# 02_PWR_IN.net
KiCad netlist of a schematic drawn in Altium Designer
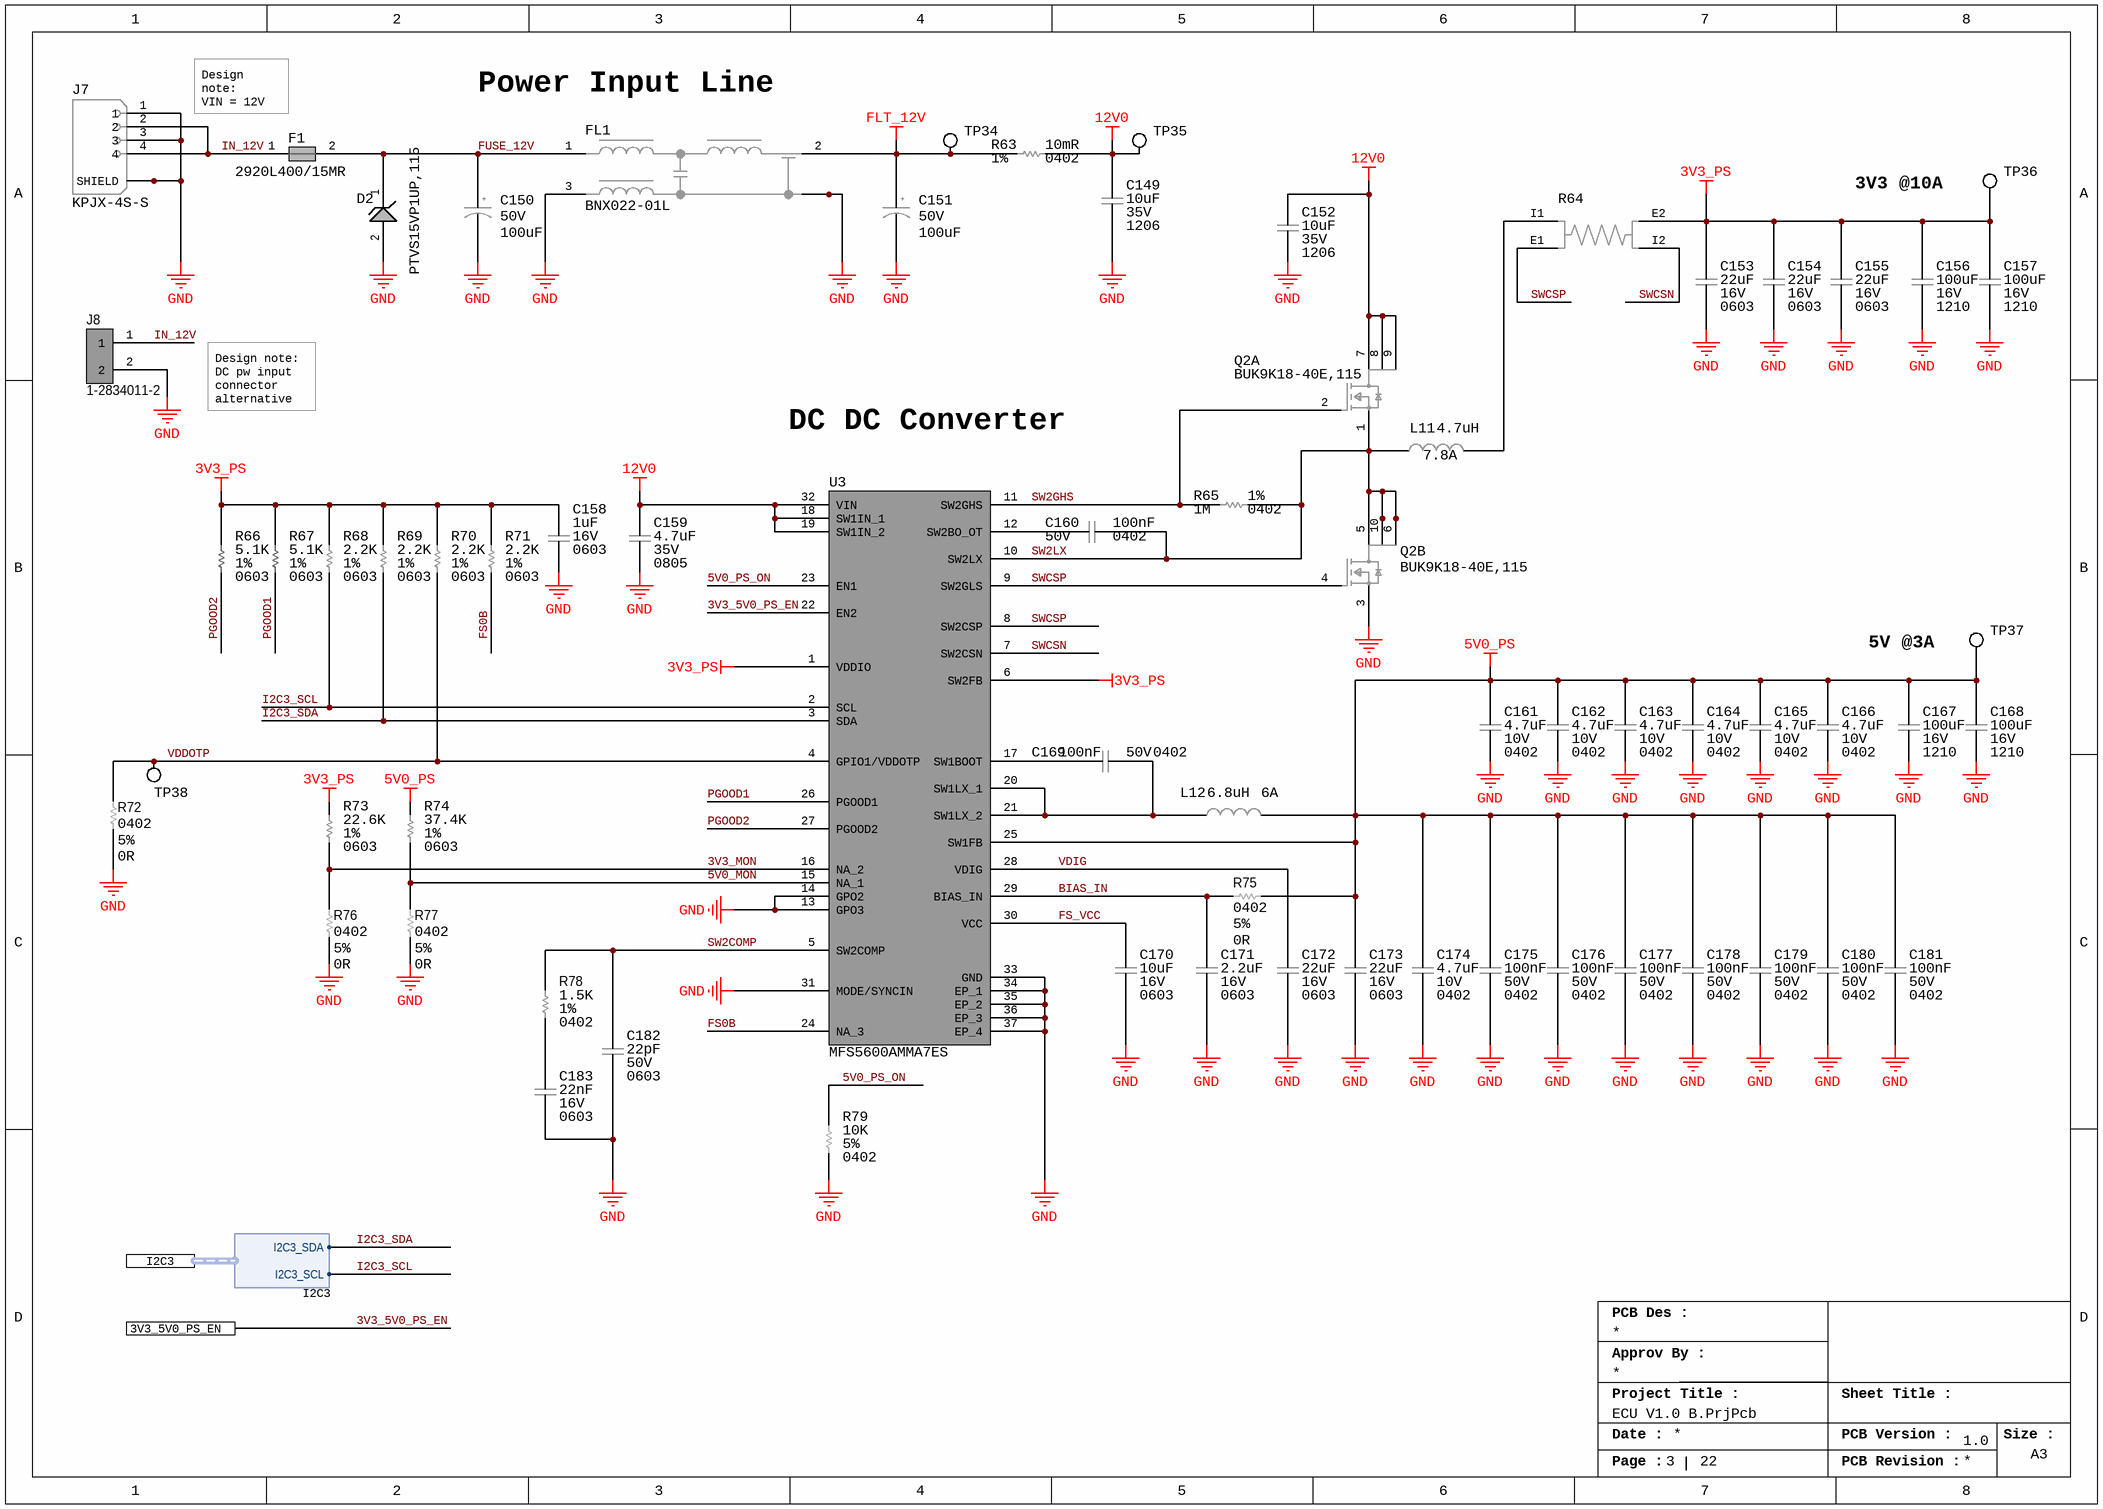
[diagram p0: 02_PWR IN.SchDoc]

(export (version "E")
  (design (tool "Eeschema 10.0.6"))
  (components
    (comp (ref "C149")
      (value "GRM319R6YA106KA12D")
      (footprint "CAP_1206_CAPC3216X16N")
      (description "1206 10 uF 35 V ±10 % Tolerance X5R SMT Multilayer Ceramic Capacitor")
      (fields
        (field (name "MANUFACTURER") "Murata")
        (field (name "TOLERANCE") "10%")
        (field (name "VOLTAGE RATING") "35V")
        (field (name "CAPACITANCE") "10uF")
        (field (name "CASE/PACKAGE") "1206")
      )
      (libsource (lib "Electronic Devices_LIB") (part "CAP_10uF_35V_X5R_1206"))
    )
    (comp (ref "C150")
      (value "UUD1H101MNL1GS")
      (footprint "CAP_POLA_UD(8X10)")
      (description "Radial Can - SMD ALUMINUM ELECTROLYTIC CAPACITOR UUD 50V 100muF ±20% 0.315Dia 8.00mm")
      (fields
        (field (name "MANUFACTURER") "Nichicon")
        (field (name "TOLERANCE") "20%")
        (field (name "VOLTAGE RATING (DC)") "50V")
        (field (name "CAPACITANCE") "100uF")
      )
      (libsource (lib "Electronic Devices_LIB") (part "CAP_100UF_50V_POL"))
    )
    (comp (ref "C151")
      (value "UUD1H101MNL1GS")
      (footprint "CAP_POLA_UD(8X10)")
      (description "Radial Can - SMD ALUMINUM ELECTROLYTIC CAPACITOR UUD 50V 100muF ±20% 0.315Dia 8.00mm")
      (fields
        (field (name "MANUFACTURER") "Nichicon")
        (field (name "TOLERANCE") "20%")
        (field (name "VOLTAGE RATING (DC)") "50V")
        (field (name "CAPACITANCE") "100uF")
      )
      (libsource (lib "Electronic Devices_LIB") (part "CAP_100UF_50V_POL"))
    )
    (comp (ref "C152")
      (value "GRM319R6YA106KA12D")
      (footprint "CAP_1206_CAPC3216X16N")
      (description "1206 10 uF 35 V ±10 % Tolerance X5R SMT Multilayer Ceramic Capacitor")
      (fields
        (field (name "MANUFACTURER") "Murata")
        (field (name "TOLERANCE") "10%")
        (field (name "VOLTAGE RATING") "35V")
        (field (name "CAPACITANCE") "10uF")
        (field (name "CASE/PACKAGE") "1206")
      )
      (libsource (lib "Electronic Devices_LIB") (part "CAP_10uF_35V_X5R_1206"))
    )
    (comp (ref "C153")
      (value "CL10A226MO7JZNC")
      (footprint "CAP_0603_CAPC1608X08N")
      (description "Cap Ceramic 22uF 16V X5R 20% Pad SMD 0603 85C T/R")
      (fields
        (field (name "MANUFACTURER") "Samsung")
        (field (name "TOLERANCE") "20%")
        (field (name "CAPACITANCE") "22uF")
        (field (name "VOLTAGE RATING") "16V")
        (field (name "CASE/PACKAGE") "0603")
      )
      (libsource (lib "Electronic Devices_LIB") (part "CAP_22UF_16V_X5R_0603"))
    )
    (comp (ref "C154")
      (value "CL10A226MO7JZNC")
      (footprint "CAP_0603_CAPC1608X08N")
      (description "Cap Ceramic 22uF 16V X5R 20% Pad SMD 0603 85C T/R")
      (fields
        (field (name "MANUFACTURER") "Samsung")
        (field (name "TOLERANCE") "20%")
        (field (name "CAPACITANCE") "22uF")
        (field (name "VOLTAGE RATING") "16V")
        (field (name "CASE/PACKAGE") "0603")
      )
      (libsource (lib "Electronic Devices_LIB") (part "CAP_22UF_16V_X5R_0603"))
    )
    (comp (ref "C155")
      (value "CL10A226MO7JZNC")
      (footprint "CAP_0603_CAPC1608X08N")
      (description "Cap Ceramic 22uF 16V X5R 20% Pad SMD 0603 85C T/R")
      (fields
        (field (name "MANUFACTURER") "Samsung")
        (field (name "TOLERANCE") "20%")
        (field (name "CAPACITANCE") "22uF")
        (field (name "VOLTAGE RATING") "16V")
        (field (name "CASE/PACKAGE") "0603")
      )
      (libsource (lib "Electronic Devices_LIB") (part "CAP_22UF_16V_X5R_0603"))
    )
    (comp (ref "C156")
      (value "EMK325ABJ107MM-T")
      (footprint "CAP_1210_CAPC3225X270N")
      (description "Multilayer Ceramic Capacitor, 100 uF, 16 V, ± 20%, X5R, 1210 [3225 Metric]")
      (fields
        (field (name "MANUFACTURER") "Taiyo Yuden")
        (field (name "TOLERANCE") "20%")
        (field (name "VOLTAGE RATING") "16V")
        (field (name "CAPACITANCE") "100uF")
        (field (name "CASE/PACKAGE") "1210")
      )
      (libsource (lib "Electronic Devices_LIB") (part "CAP_100UF_16V_X5R_1210"))
    )
    (comp (ref "C157")
      (value "EMK325ABJ107MM-T")
      (footprint "CAP_1210_CAPC3225X270N")
      (description "Multilayer Ceramic Capacitor, 100 uF, 16 V, ± 20%, X5R, 1210 [3225 Metric]")
      (fields
        (field (name "MANUFACTURER") "Taiyo Yuden")
        (field (name "TOLERANCE") "20%")
        (field (name "VOLTAGE RATING") "16V")
        (field (name "CAPACITANCE") "100uF")
        (field (name "CASE/PACKAGE") "1210")
      )
      (libsource (lib "Electronic Devices_LIB") (part "CAP_100UF_16V_X5R_1210"))
    )
    (comp (ref "C158")
      (value "CL10A105KO8NNNC")
      (footprint "CAP_0603_CAPC1608X08N")
      (description "CAP CER 1UF 16V X5R 0603")
      (fields
        (field (name "MANUFACTURER") "Samsung")
        (field (name "TOLERANCE") "10%")
        (field (name "VOLTAGE RATING") "16V")
        (field (name "CAPACITANCE") "1uF")
        (field (name "CASE/PACKAGE") "0603")
      )
      (libsource (lib "Electronic Devices_LIB") (part "CAP_1UF_16V_X5R_0603"))
    )
    (comp (ref "C159")
      (value "CL21A475KLCLQNC")
      (footprint "CAP_0805_CAPC2012X12N")
      (description "CL Series 0805 35 V 4.7 uF ±10% Tolerance X5R Multilayer Ceramic Chip Capacitor")
      (fields
        (field (name "MANUFACTURER") "Samsung")
        (field (name "TOLERANCE") "10%")
        (field (name "VOLTAGE RATING") "35V")
        (field (name "CAPACITANCE") "4.7uF")
        (field (name "CASE/PACKAGE") "0805")
      )
      (libsource (lib "Electronic Devices_LIB") (part "CAP_4.7uF_35V_X5R_0805"))
    )
    (comp (ref "C160")
      (value "GRM155R71H104KE14D")
      (footprint "CAP_0402_CAPC1005X05N")
      (description "Multilayer Ceramic Capacitor, 0.1 uF, 16 V, ± 10%, X7R, 0402 [1005 Metric]")
      (fields
        (field (name "MANUFACTURER") "Murata")
        (field (name "TOLERANCE") "10%")
        (field (name "VOLTAGE RATING") "50V")
        (field (name "CAPACITANCE") "100nF")
        (field (name "CASE/PACKAGE") "0402")
      )
      (libsource (lib "Electronic Devices_LIB") (part "CAP_100NF_50V_X7R_0402"))
    )
    (comp (ref "C161")
      (value "CL05A475KP5NRNC")
      (footprint "CAP_0402_CAPC1005X05N")
      (description "Multilayer Ceramic Capacitor, 4.7 uF, 10 V, ± 10%, X5R, 0402 [1005 Metric]")
      (fields
        (field (name "MANUFACTURER") "Samsung")
        (field (name "TOLERANCE") "10%")
        (field (name "CAPACITANCE") "4.7uF")
        (field (name "VOLTAGE RATING") "10V")
        (field (name "CASE/PACKAGE") "0402")
      )
      (libsource (lib "Electronic Devices_LIB") (part "CAP_4.7UF_10V_X5R_0402"))
    )
    (comp (ref "C162")
      (value "CL05A475KP5NRNC")
      (footprint "CAP_0402_CAPC1005X05N")
      (description "Multilayer Ceramic Capacitor, 4.7 uF, 10 V, ± 10%, X5R, 0402 [1005 Metric]")
      (fields
        (field (name "MANUFACTURER") "Samsung")
        (field (name "TOLERANCE") "10%")
        (field (name "CAPACITANCE") "4.7uF")
        (field (name "VOLTAGE RATING") "10V")
        (field (name "CASE/PACKAGE") "0402")
      )
      (libsource (lib "Electronic Devices_LIB") (part "CAP_4.7UF_10V_X5R_0402"))
    )
    (comp (ref "C163")
      (value "CL05A475KP5NRNC")
      (footprint "CAP_0402_CAPC1005X05N")
      (description "Multilayer Ceramic Capacitor, 4.7 uF, 10 V, ± 10%, X5R, 0402 [1005 Metric]")
      (fields
        (field (name "MANUFACTURER") "Samsung")
        (field (name "TOLERANCE") "10%")
        (field (name "CAPACITANCE") "4.7uF")
        (field (name "VOLTAGE RATING") "10V")
        (field (name "CASE/PACKAGE") "0402")
      )
      (libsource (lib "Electronic Devices_LIB") (part "CAP_4.7UF_10V_X5R_0402"))
    )
    (comp (ref "C164")
      (value "CL05A475KP5NRNC")
      (footprint "CAP_0402_CAPC1005X05N")
      (description "Multilayer Ceramic Capacitor, 4.7 uF, 10 V, ± 10%, X5R, 0402 [1005 Metric]")
      (fields
        (field (name "MANUFACTURER") "Samsung")
        (field (name "TOLERANCE") "10%")
        (field (name "CAPACITANCE") "4.7uF")
        (field (name "VOLTAGE RATING") "10V")
        (field (name "CASE/PACKAGE") "0402")
      )
      (libsource (lib "Electronic Devices_LIB") (part "CAP_4.7UF_10V_X5R_0402"))
    )
    (comp (ref "C165")
      (value "CL05A475KP5NRNC")
      (footprint "CAP_0402_CAPC1005X05N")
      (description "Multilayer Ceramic Capacitor, 4.7 uF, 10 V, ± 10%, X5R, 0402 [1005 Metric]")
      (fields
        (field (name "MANUFACTURER") "Samsung")
        (field (name "TOLERANCE") "10%")
        (field (name "CAPACITANCE") "4.7uF")
        (field (name "VOLTAGE RATING") "10V")
        (field (name "CASE/PACKAGE") "0402")
      )
      (libsource (lib "Electronic Devices_LIB") (part "CAP_4.7UF_10V_X5R_0402"))
    )
    (comp (ref "C166")
      (value "CL05A475KP5NRNC")
      (footprint "CAP_0402_CAPC1005X05N")
      (description "Multilayer Ceramic Capacitor, 4.7 uF, 10 V, ± 10%, X5R, 0402 [1005 Metric]")
      (fields
        (field (name "MANUFACTURER") "Samsung")
        (field (name "TOLERANCE") "10%")
        (field (name "CAPACITANCE") "4.7uF")
        (field (name "VOLTAGE RATING") "10V")
        (field (name "CASE/PACKAGE") "0402")
      )
      (libsource (lib "Electronic Devices_LIB") (part "CAP_4.7UF_10V_X5R_0402"))
    )
    (comp (ref "C167")
      (value "EMK325ABJ107MM-T")
      (footprint "CAP_1210_CAPC3225X270N")
      (description "Multilayer Ceramic Capacitor, 100 uF, 16 V, ± 20%, X5R, 1210 [3225 Metric]")
      (fields
        (field (name "MANUFACTURER") "Taiyo Yuden")
        (field (name "TOLERANCE") "20%")
        (field (name "VOLTAGE RATING") "16V")
        (field (name "CAPACITANCE") "100uF")
        (field (name "CASE/PACKAGE") "1210")
      )
      (libsource (lib "Electronic Devices_LIB") (part "CAP_100UF_16V_X5R_1210"))
    )
    (comp (ref "C168")
      (value "EMK325ABJ107MM-T")
      (footprint "CAP_1210_CAPC3225X270N")
      (description "Multilayer Ceramic Capacitor, 100 uF, 16 V, ± 20%, X5R, 1210 [3225 Metric]")
      (fields
        (field (name "MANUFACTURER") "Taiyo Yuden")
        (field (name "TOLERANCE") "20%")
        (field (name "VOLTAGE RATING") "16V")
        (field (name "CAPACITANCE") "100uF")
        (field (name "CASE/PACKAGE") "1210")
      )
      (libsource (lib "Electronic Devices_LIB") (part "CAP_100UF_16V_X5R_1210"))
    )
    (comp (ref "C169")
      (value "GRM155R71H104KE14D")
      (footprint "CAP_0402_CAPC1005X05N")
      (description "Multilayer Ceramic Capacitor, 0.1 uF, 16 V, ± 10%, X7R, 0402 [1005 Metric]")
      (fields
        (field (name "MANUFACTURER") "Murata")
        (field (name "TOLERANCE") "10%")
        (field (name "VOLTAGE RATING") "50V")
        (field (name "CAPACITANCE") "100nF")
        (field (name "CASE/PACKAGE") "0402")
      )
      (libsource (lib "Electronic Devices_LIB") (part "CAP_100NF_50V_X7R_0402"))
    )
    (comp (ref "C170")
      (value "GRM188R61C106MAALD")
      (footprint "CAP_0603_CAPC1608X08N")
      (description "0603 10 uF 16 V ±20% Tolerance X5R Multilayer Ceramic Chip Capacitor")
      (fields
        (field (name "MANUFACTURER") "Murata")
        (field (name "TOLERANCE") "20%")
        (field (name "VOLTAGE RATING") "16V")
        (field (name "CAPACITANCE") "10uF")
        (field (name "CASE/PACKAGE") "0603")
      )
      (libsource (lib "Electronic Devices_LIB") (part "CAP_10UF_16V_X5R_0603"))
    )
    (comp (ref "C171")
      (value "EMK107BB7225KA-T")
      (footprint "CAP_0603_CAPC1608X08N")
      (description "Multilayer Ceramic Capacitors (High dielectric type), 16V, 2.2 uF, ± 10 %, 0603, X7R, RoHS")
      (fields
        (field (name "MANUFACTURER") "Taiyo Yuden")
        (field (name "TOLERANCE") "10%")
        (field (name "CASE/PACKAGE") "0603")
        (field (name "CAPACITANCE") "2.2uF")
        (field (name "VOLTAGE RATING") "16V")
      )
      (libsource (lib "Electronic Devices_LIB") (part "CAP_2.2UF_16V_X7R_0603"))
    )
    (comp (ref "C172")
      (value "CL10A226MO7JZNC")
      (footprint "CAP_0603_CAPC1608X08N")
      (description "Cap Ceramic 22uF 16V X5R 20% Pad SMD 0603 85C T/R")
      (fields
        (field (name "MANUFACTURER") "Samsung")
        (field (name "TOLERANCE") "20%")
        (field (name "CAPACITANCE") "22uF")
        (field (name "VOLTAGE RATING") "16V")
        (field (name "CASE/PACKAGE") "0603")
      )
      (libsource (lib "Electronic Devices_LIB") (part "CAP_22UF_16V_X5R_0603"))
    )
    (comp (ref "C173")
      (value "CL10A226MO7JZNC")
      (footprint "CAP_0603_CAPC1608X08N")
      (description "Cap Ceramic 22uF 16V X5R 20% Pad SMD 0603 85C T/R")
      (fields
        (field (name "MANUFACTURER") "Samsung")
        (field (name "TOLERANCE") "20%")
        (field (name "CAPACITANCE") "22uF")
        (field (name "VOLTAGE RATING") "16V")
        (field (name "CASE/PACKAGE") "0603")
      )
      (libsource (lib "Electronic Devices_LIB") (part "CAP_22UF_16V_X5R_0603"))
    )
    (comp (ref "C174")
      (value "CL05A475KP5NRNC")
      (footprint "CAP_0402_CAPC1005X05N")
      (description "Multilayer Ceramic Capacitor, 4.7 uF, 10 V, ± 10%, X5R, 0402 [1005 Metric]")
      (fields
        (field (name "MANUFACTURER") "Samsung")
        (field (name "TOLERANCE") "10%")
        (field (name "CAPACITANCE") "4.7uF")
        (field (name "VOLTAGE RATING") "10V")
        (field (name "CASE/PACKAGE") "0402")
      )
      (libsource (lib "Electronic Devices_LIB") (part "CAP_4.7UF_10V_X5R_0402"))
    )
    (comp (ref "C175")
      (value "GRM155R71H104KE14D")
      (footprint "CAP_0402_CAPC1005X05N")
      (description "Multilayer Ceramic Capacitor, 0.1 uF, 16 V, ± 10%, X7R, 0402 [1005 Metric]")
      (fields
        (field (name "MANUFACTURER") "Murata")
        (field (name "TOLERANCE") "10%")
        (field (name "VOLTAGE RATING") "50V")
        (field (name "CAPACITANCE") "100nF")
        (field (name "CASE/PACKAGE") "0402")
      )
      (libsource (lib "Electronic Devices_LIB") (part "CAP_100NF_50V_X7R_0402"))
    )
    (comp (ref "C176")
      (value "GRM155R71H104KE14D")
      (footprint "CAP_0402_CAPC1005X05N")
      (description "Multilayer Ceramic Capacitor, 0.1 uF, 16 V, ± 10%, X7R, 0402 [1005 Metric]")
      (fields
        (field (name "MANUFACTURER") "Murata")
        (field (name "TOLERANCE") "10%")
        (field (name "VOLTAGE RATING") "50V")
        (field (name "CAPACITANCE") "100nF")
        (field (name "CASE/PACKAGE") "0402")
      )
      (libsource (lib "Electronic Devices_LIB") (part "CAP_100NF_50V_X7R_0402"))
    )
    (comp (ref "C177")
      (value "GRM155R71H104KE14D")
      (footprint "CAP_0402_CAPC1005X05N")
      (description "Multilayer Ceramic Capacitor, 0.1 uF, 16 V, ± 10%, X7R, 0402 [1005 Metric]")
      (fields
        (field (name "MANUFACTURER") "Murata")
        (field (name "TOLERANCE") "10%")
        (field (name "VOLTAGE RATING") "50V")
        (field (name "CAPACITANCE") "100nF")
        (field (name "CASE/PACKAGE") "0402")
      )
      (libsource (lib "Electronic Devices_LIB") (part "CAP_100NF_50V_X7R_0402"))
    )
    (comp (ref "C178")
      (value "GRM155R71H104KE14D")
      (footprint "CAP_0402_CAPC1005X05N")
      (description "Multilayer Ceramic Capacitor, 0.1 uF, 16 V, ± 10%, X7R, 0402 [1005 Metric]")
      (fields
        (field (name "MANUFACTURER") "Murata")
        (field (name "TOLERANCE") "10%")
        (field (name "VOLTAGE RATING") "50V")
        (field (name "CAPACITANCE") "100nF")
        (field (name "CASE/PACKAGE") "0402")
      )
      (libsource (lib "Electronic Devices_LIB") (part "CAP_100NF_50V_X7R_0402"))
    )
    (comp (ref "C179")
      (value "GRM155R71H104KE14D")
      (footprint "CAP_0402_CAPC1005X05N")
      (description "Multilayer Ceramic Capacitor, 0.1 uF, 16 V, ± 10%, X7R, 0402 [1005 Metric]")
      (fields
        (field (name "MANUFACTURER") "Murata")
        (field (name "TOLERANCE") "10%")
        (field (name "VOLTAGE RATING") "50V")
        (field (name "CAPACITANCE") "100nF")
        (field (name "CASE/PACKAGE") "0402")
      )
      (libsource (lib "Electronic Devices_LIB") (part "CAP_100NF_50V_X7R_0402"))
    )
    (comp (ref "C180")
      (value "GRM155R71H104KE14D")
      (footprint "CAP_0402_CAPC1005X05N")
      (description "Multilayer Ceramic Capacitor, 0.1 uF, 16 V, ± 10%, X7R, 0402 [1005 Metric]")
      (fields
        (field (name "MANUFACTURER") "Murata")
        (field (name "TOLERANCE") "10%")
        (field (name "VOLTAGE RATING") "50V")
        (field (name "CAPACITANCE") "100nF")
        (field (name "CASE/PACKAGE") "0402")
      )
      (libsource (lib "Electronic Devices_LIB") (part "CAP_100NF_50V_X7R_0402"))
    )
    (comp (ref "C181")
      (value "GRM155R71H104KE14D")
      (footprint "CAP_0402_CAPC1005X05N")
      (description "Multilayer Ceramic Capacitor, 0.1 uF, 16 V, ± 10%, X7R, 0402 [1005 Metric]")
      (fields
        (field (name "MANUFACTURER") "Murata")
        (field (name "TOLERANCE") "10%")
        (field (name "VOLTAGE RATING") "50V")
        (field (name "CAPACITANCE") "100nF")
        (field (name "CASE/PACKAGE") "0402")
      )
      (libsource (lib "Electronic Devices_LIB") (part "CAP_100NF_50V_X7R_0402"))
    )
    (comp (ref "C182")
      (value "C0603C220J5GACTU")
      (footprint "CAP_0603_CAPC1608X08N")
      (description "Multilayer Ceramic Capacitor, 22 pF, 50 V, ï¿½ 5%, C0G (NP0), 0603 [1608 Metric]")
      (fields
        (field (name "MANUFACTURER") "KEMET")
        (field (name "TOLERANCE") "5%")
        (field (name "VOLTAGE RATING (DC)") "50V")
        (field (name "CAPACITANCE") "22pF")
        (field (name "CASE/PACKAGE") "0603")
      )
      (libsource (lib "Electronic Devices_LIB") (part "CAP_22pF_50V_NP0_0603"))
    )
    (comp (ref "C183")
      (value "C0603C223K4RACTU")
      (footprint "CAP_0603_CAPC1608X08N")
      (description "Multilayer Ceramic Capacitor, 0.022 uF, 16 V, ± 10%, X7R, 0603 [1608 Metric]")
      (fields
        (field (name "MANUFACTURER") "KEMET")
        (field (name "TOLERANCE") "10%")
        (field (name "VOLTAGE RATING (DC)") "16V")
        (field (name "CAPACITANCE") "22nF")
        (field (name "CASE/PACKAGE") "0603")
      )
      (libsource (lib "Electronic Devices_LIB") (part "CAP_22nF_16V_X7R_0603"))
    )
    (comp (ref "D2")
      (value "PTVS15VP1UP,115")
      (footprint "PMEG3050EP115")
      (description "TVS DIODE 15VWM 24.4VC SOD128")
      (fields (field (name "MANUFACTURER") "Nexperia"))
      (libsource (lib "Electronic Devices_LIB") (part "DIO_TVS_24.4V_PTVS15VP1UP,115"))
    )
    (comp (ref "F1")
      (value "2920L400/15MR")
      (footprint "2920L07560MR")
      (description "PTC Resettable Fuse 4A(hold) 8A(trip) 15VDC 40A 1.5W 4s 0.01Ohm SMD Solder Pad 2920 T/R")
      (fields (field (name "MANUFACTURER") "Littelfuse"))
      (libsource (lib "Electronic Devices_LIB") (part "FUSE_PTC_8A_2920L400/15MR"))
    )
    (comp (ref "FL1")
      (value "BNX022-01L")
      (footprint "FILTER_BNX022-01L")
      (description "EMI Filter 1MHz to 1000MHz 35dB 10A 50VDC Flat Style SMD Embossed T/R")
      (fields (field (name "MANUFACTURER") "Murata"))
      (libsource (lib "Electronic Devices_LIB") (part "FILTER_EMI_50VDC_10A_BNX022-01L"))
    )
    (comp (ref "J7")
      (value "KPJX-4S-S")
      (footprint "CONN_DC_KYCON_KPJX-4S-S")
      (description "Conn Power SKT 4 POS Solder ST Thru-Hole 4 Terminal 1 Port")
      (fields (field (name "MANUFACTURER") "Kycon"))
      (libsource (lib "Electronic Devices_LIB") (part "CONN_DC_JACK_PWR_KPJX-4S-S"))
    )
    (comp (ref "J8")
      (value "1-2834011-2")
      (footprint "CONN_TBLOCK_128340112")
      (description "2POS3.5MMTOPENTRYSCREWLESSC")
      (fields (field (name "MANUFACTURER") "TE Connectivity") (field (name "VOLTAGE") "300V"))
      (libsource (lib "Electronic Devices_LIB") (part "CONN_TBLOCK_2P_3.5mm_1-2834011-2"))
    )
    (comp (ref "L11")
      (value "SPM7054VT-4R7M-D")
      (footprint "SPM7054VT")
      (description "Inductor Power Shielded Wirewound 4.7uH 20% 100KHz Metal 7.8A 0.01826Ohm DCR Automotive T/R")
      (fields
        (field (name "MANUFACTURER") "TDK")
        (field (name "CURRENT RATING") "7.8A")
        (field (name "INDUCTANCE") "4.7uH")
      )
      (libsource (lib "Electronic Devices_LIB") (part "IND_4.7uH_7.8A_SPM7054VT-4R7M-D"))
    )
    (comp (ref "L12")
      (value "74437368068")
      (footprint "WE-LHMI_104048")
      (description "WE-LHMI; 6800 nH; Composite Iron Multilayer SMD Inductor; 1040 Case; .013GHz 6A")
      (fields
        (field (name "MANUFACTURER") "Wurth Electronics")
        (field (name "TOLERANCE") "20%")
        (field (name "MAX DC CURRENT") "6A")
        (field (name "INDUCTANCE") "6.8uH")
      )
      (libsource (lib "Electronic Devices_LIB") (part "IND_6.8uH_6A_74437368068"))
    )
    (comp (ref "Q2")
      (value "BUK9K18-40E,115")
      (footprint "BUK9K1840E115")
      (description "Transistor MOSFET Array Dual N -CH 40V 30A 8-Pin LFPAK-56D T/R")
      (fields (field (name "MANUFACTURER") "Nexperia"))
      (libsource (lib "Electronic Devices_LIB") (part "TRANS_FET_CH__N_40V_30A_BUK9K18-40E,115"))
    )
    (comp (ref "R63")
      (value "ERJ-2LWFR010X")
      (footprint "RES_0603_RESC1608X04N")
      (description "Res Current Sense Thick Film 0402 0.01 Ohm 1% 1/5W 0ppm/°C to 500ppm/°C Molded T/R")
      (fields
        (field (name "MANUFACTURER") "Panasonic")
        (field (name "TOLERANCE") "1%")
        (field (name "RESISTANCE") "10mR")
        (field (name "CASE/PACKAGE") "0402")
      )
      (libsource (lib "Electronic Devices_LIB") (part "RES_10mR_1%_0.05W_0402"))
    )
    (comp (ref "R64")
      (value "WSK2512R0100FEA")
      (footprint "RES_WSK2512R0100FEA")
      (description "Fixed Resistor, Metal Strip, 1W, 0.01ohm, 0.1V, 1% +/-Tol, 35ppm/Cel, Surface Mount, 2512")
      (fields (field (name "MANUFACTURER") "Vishay") (field (name "TOLERANCE") "1%"))
      (libsource (lib "Electronic Devices_LIB") (part "RES_10mR_1%_1W_2512"))
    )
    (comp (ref "R65")
      (value "CR0402-FX-1004GLF")
      (footprint "RES_0402_RESC1005X04N")
      (description "Res Thick Film 0402 1M Ohm 1% 1/16W ±100ppm/°C Molded SMD SMD Paper Tape on Plastic Reel")
      (fields
        (field (name "MANUFACTURER") "Bourns")
        (field (name "RESISTANCE") "1M")
        (field (name "TOLERANCE") "1%")
        (field (name "CASE/PACKAGE") "0402")
      )
      (libsource (lib "Electronic Devices_LIB") (part "RES_1M_1%_63mW_0402"))
    )
    (comp (ref "R66")
      (value "RC0603FR-075K1L")
      (footprint "RES_0603_RESC1608X04N")
      (description "SMD Chip Resistor, 5.1 kOhm, ± 1%, 100 mW, 0603 [1608 Metric], Thick Film, General Purpose")
      (fields
        (field (name "MANUFACTURER") "Yageo")
        (field (name "TOLERANCE") "1%")
        (field (name "RESISTANCE") "5.1K")
        (field (name "CASE/PACKAGE") "0603")
      )
      (libsource (lib "Electronic Devices_LIB") (part "RES_5.1K_1%_100mW_0603"))
    )
    (comp (ref "R67")
      (value "RC0603FR-075K1L")
      (footprint "RES_0603_RESC1608X04N")
      (description "SMD Chip Resistor, 5.1 kOhm, ± 1%, 100 mW, 0603 [1608 Metric], Thick Film, General Purpose")
      (fields
        (field (name "MANUFACTURER") "Yageo")
        (field (name "TOLERANCE") "1%")
        (field (name "RESISTANCE") "5.1K")
        (field (name "CASE/PACKAGE") "0603")
      )
      (libsource (lib "Electronic Devices_LIB") (part "RES_5.1K_1%_100mW_0603"))
    )
    (comp (ref "R68")
      (value "RC0603FR-072K2L")
      (footprint "RES_0603_RESC1608X04N")
      (description "SMD Chip Resistor, 2.2 Kohm, ½ 1%, 100 Mw, 0603 [1608 Metric], Thick Film, General Purpose")
      (fields
        (field (name "MANUFACTURER") "Yageo")
        (field (name "TOLERANCE") "1%")
        (field (name "RESISTANCE") "2.2K")
        (field (name "CASE/PACKAGE") "0603")
      )
      (libsource (lib "Electronic Devices_LIB") (part "RES_2.2K_1%_100mW_0603"))
    )
    (comp (ref "R69")
      (value "RC0603FR-072K2L")
      (footprint "RES_0603_RESC1608X04N")
      (description "SMD Chip Resistor, 2.2 Kohm, ½ 1%, 100 Mw, 0603 [1608 Metric], Thick Film, General Purpose")
      (fields
        (field (name "MANUFACTURER") "Yageo")
        (field (name "TOLERANCE") "1%")
        (field (name "RESISTANCE") "2.2K")
        (field (name "CASE/PACKAGE") "0603")
      )
      (libsource (lib "Electronic Devices_LIB") (part "RES_2.2K_1%_100mW_0603"))
    )
    (comp (ref "R70")
      (value "RC0603FR-072K2L")
      (footprint "RES_0603_RESC1608X04N")
      (description "SMD Chip Resistor, 2.2 Kohm, ½ 1%, 100 Mw, 0603 [1608 Metric], Thick Film, General Purpose")
      (fields
        (field (name "MANUFACTURER") "Yageo")
        (field (name "TOLERANCE") "1%")
        (field (name "RESISTANCE") "2.2K")
        (field (name "CASE/PACKAGE") "0603")
      )
      (libsource (lib "Electronic Devices_LIB") (part "RES_2.2K_1%_100mW_0603"))
    )
    (comp (ref "R71")
      (value "RC0603FR-072K2L")
      (footprint "RES_0603_RESC1608X04N")
      (description "SMD Chip Resistor, 2.2 Kohm, ½ 1%, 100 Mw, 0603 [1608 Metric], Thick Film, General Purpose")
      (fields
        (field (name "MANUFACTURER") "Yageo")
        (field (name "TOLERANCE") "1%")
        (field (name "RESISTANCE") "2.2K")
        (field (name "CASE/PACKAGE") "0603")
      )
      (libsource (lib "Electronic Devices_LIB") (part "RES_2.2K_1%_100mW_0603"))
    )
    (comp (ref "R72")
      (value "ERJ-2GE0R00X")
      (footprint "RES_0402_RESC1005X04N")
      (description "SMD Chip Resistor, Jumper, 0 ohm, 100 mW, 0402 [1005 Metric], Thick Film, General Purpose")
      (fields
        (field (name "MANUFACTURER") "Panasonic")
        (field (name "CASE CODE (IMPERIAL)") "0402")
        (field (name "TOLERANCE") "5%")
        (field (name "RESISTANCE") "0R")
      )
      (libsource (lib "Electronic Devices_LIB") (part "RES_0R_5%_100mW_0402"))
    )
    (comp (ref "R73")
      (value "AC0603FR-0722K6L")
      (footprint "RES_0603_RESC1608X04N")
      (description "Res Thick Film 0603 22.6K Ohm 1% 0.1W(1/10W) ±100ppm/C Pad SMD Automotive T/R")
      (fields
        (field (name "MANUFACTURER") "Yageo")
        (field (name "TOLERANCE") "1%")
        (field (name "RESISTANCE") "22.6K")
        (field (name "CASE/PACKAGE") "0603")
      )
      (libsource (lib "Electronic Devices_LIB") (part "RES_22.6K_1%_100mW_0603"))
    )
    (comp (ref "R74")
      (value "RC0603FR-0737K4L")
      (footprint "RES_0603_RESC1608X04N")
      (description "SMD Chip Resistor, 37.4 kOhm, ± 1%, 100 mW, 0603 [1608 Metric], Thick Film, General Purpose")
      (fields
        (field (name "MANUFACTURER") "Yageo")
        (field (name "TOLERANCE") "1%")
        (field (name "RESISTANCE") "37.4K")
        (field (name "CASE/PACKAGE") "0603")
      )
      (libsource (lib "Electronic Devices_LIB") (part "RES_37.4K_1%_100mW_0603"))
    )
    (comp (ref "R75")
      (value "ERJ-2GE0R00X")
      (footprint "RES_0402_RESC1005X04N")
      (description "SMD Chip Resistor, Jumper, 0 ohm, 100 mW, 0402 [1005 Metric], Thick Film, General Purpose")
      (fields
        (field (name "MANUFACTURER") "Panasonic")
        (field (name "CASE CODE (IMPERIAL)") "0402")
        (field (name "TOLERANCE") "5%")
        (field (name "RESISTANCE") "0R")
      )
      (libsource (lib "Electronic Devices_LIB") (part "RES_0R_5%_100mW_0402"))
    )
    (comp (ref "R76")
      (value "ERJ-2GE0R00X")
      (footprint "RES_0402_RESC1005X04N")
      (description "SMD Chip Resistor, Jumper, 0 ohm, 100 mW, 0402 [1005 Metric], Thick Film, General Purpose")
      (fields
        (field (name "MANUFACTURER") "Panasonic")
        (field (name "CASE CODE (IMPERIAL)") "0402")
        (field (name "TOLERANCE") "5%")
        (field (name "RESISTANCE") "0R")
      )
      (libsource (lib "Electronic Devices_LIB") (part "RES_0R_5%_100mW_0402"))
    )
    (comp (ref "R77")
      (value "ERJ-2GE0R00X")
      (footprint "RES_0402_RESC1005X04N")
      (description "SMD Chip Resistor, Jumper, 0 ohm, 100 mW, 0402 [1005 Metric], Thick Film, General Purpose")
      (fields
        (field (name "MANUFACTURER") "Panasonic")
        (field (name "CASE CODE (IMPERIAL)") "0402")
        (field (name "TOLERANCE") "5%")
        (field (name "RESISTANCE") "0R")
      )
      (libsource (lib "Electronic Devices_LIB") (part "RES_0R_5%_100mW_0402"))
    )
    (comp (ref "R78")
      (value "CR0402-FX-1501GLF")
      (footprint "RES_0402_RESC1005X04N")
      (description "Res Thick Film 0402 1.5K Ohm 1% 1/16W ±100ppm/°C Molded SMD SMD Paper Tape on Plastic Reel")
      (fields
        (field (name "MANUFACTURER") "Bourns")
        (field (name "RESISTANCE") "1.5K")
        (field (name "TOLERANCE") "1%")
        (field (name "CASE/PACKAGE") "0402")
      )
      (libsource (lib "Electronic Devices_LIB") (part "RES_1.5K_1%_63mW_0402"))
    )
    (comp (ref "R79")
      (value "ERJ-2GEJ103X")
      (footprint "RES_0402_RESC1005X04N")
      (description "Res Thick Film 0402 10K Ohm 5% 1/10W ±200ppm/°C Molded SMD Punched Carrier T/R")
      (fields
        (field (name "MANUFACTURER") "Panasonic")
        (field (name "TOLERANCE") "5%")
        (field (name "RESISTANCE") "10K")
        (field (name "CASE/PACKAGE") "0402")
      )
      (libsource (lib "Electronic Devices_LIB") (part "RES_10K_5%_100mW_0402"))
    )
    (comp (ref "TP34")
      (value "NO COMPONENT")
      (footprint "TP_PAD_0.5MM_SMD_ROUND")
      (description "Test Point, SMD pad, round, 1.5mm, 1.6mm, 3mm diameter")
      (libsource (lib "Electronic Devices_LIB") (part "TP_PAD_SMD_SMALL"))
    )
    (comp (ref "TP35")
      (value "NO COMPONENT")
      (footprint "TP_PAD_0.5MM_SMD_ROUND")
      (description "Test Point, SMD pad, round, 1.5mm, 1.6mm, 3mm diameter")
      (libsource (lib "Electronic Devices_LIB") (part "TP_PAD_SMD_SMALL"))
    )
    (comp (ref "TP36")
      (value "NO COMPONENT")
      (footprint "TP_PAD_0.5MM_SMD_ROUND")
      (description "Test Point, SMD pad, round, 1.5mm, 1.6mm, 3mm diameter")
      (libsource (lib "Electronic Devices_LIB") (part "TP_PAD_SMD_SMALL"))
    )
    (comp (ref "TP37")
      (value "NO COMPONENT")
      (footprint "TP_PAD_0.5MM_SMD_ROUND")
      (description "Test Point, SMD pad, round, 1.5mm, 1.6mm, 3mm diameter")
      (libsource (lib "Electronic Devices_LIB") (part "TP_PAD_SMD_SMALL"))
    )
    (comp (ref "TP38")
      (value "NO COMPONENT")
      (footprint "TP_PAD_0.5MM_SMD_ROUND")
      (description "Test Point, SMD pad, round, 1.5mm, 1.6mm, 3mm diameter")
      (libsource (lib "Electronic Devices_LIB") (part "TP_PAD_SMD_SMALL"))
    )
    (comp (ref "U3")
      (value "MFS5600AMMA7ES")
      (footprint "MFS5600AMMA7ES")
      (description "Power Management, 36 V, 2 Step-Down DC-DC Converters, 2 Regulated Outputs, 32 Pins, HVQFN-EP")
      (fields (field (name "MANUFACTURER") "NXP Semiconductors"))
      (libsource (lib "Electronic Devices_LIB") (part "IC_REG_BUCK_MFS5600AMMA7ES"))
    )
  )
  (nets
    (net (code "2") (name "/3V3_5V0_PS_EN") (class "Default")
      (node (ref "U3") (pin "22") (pinfunction "EN2_22") (pintype "passive"))
    )
    (net (code "3") (name "/3V3_MON") (class "Default")
      (node (ref "R73") (pin "1") (pinfunction "1_1") (pintype "passive"))
      (node (ref "R76") (pin "2") (pinfunction "2_2") (pintype "passive"))
      (node (ref "U3") (pin "16") (pinfunction "NA_2_16") (pintype "passive"))
    )
    (net (code "4") (name "/5V0_MON") (class "Default")
      (node (ref "R74") (pin "1") (pinfunction "1_1") (pintype "passive"))
      (node (ref "R77") (pin "2") (pinfunction "2_2") (pintype "passive"))
      (node (ref "U3") (pin "15") (pinfunction "NA_1_15") (pintype "passive"))
    )
    (net (code "5") (name "/5V0_PS_ON") (class "Default")
      (node (ref "R79") (pin "1") (pinfunction "1_1") (pintype "passive"))
      (node (ref "U3") (pin "23") (pinfunction "EN1_23") (pintype "passive"))
    )
    (net (code "6") (name "/BIAS_IN") (class "Default")
      (node (ref "C171") (pin "2") (pinfunction "2_2") (pintype "passive"))
      (node (ref "R75") (pin "2") (pinfunction "2_2") (pintype "passive"))
      (node (ref "U3") (pin "29") (pinfunction "BIAS_IN_29") (pintype "passive"))
    )
    (net (code "7") (name "/FS0B") (class "Default")
      (node (ref "R71") (pin "1") (pinfunction "1_1") (pintype "passive"))
      (node (ref "U3") (pin "24") (pinfunction "NA_3_24") (pintype "passive"))
    )
    (net (code "8") (name "/FS_VCC") (class "Default")
      (node (ref "C170") (pin "2") (pinfunction "2_2") (pintype "passive"))
      (node (ref "U3") (pin "30") (pinfunction "VCC_30") (pintype "passive"))
    )
    (net (code "9") (name "/FUSE_12V") (class "Default")
      (node (ref "C150") (pin "1") (pinfunction "1_1") (pintype "passive"))
      (node (ref "D2") (pin "1") (pinfunction "K_1") (pintype "passive"))
      (node (ref "F1") (pin "2") (pinfunction "2_2") (pintype "passive"))
      (node (ref "FL1") (pin "1") (pinfunction "B_1") (pintype "passive"))
    )
    (net (code "10") (name "/I2C3_SCL") (class "Default")
      (node (ref "R68") (pin "1") (pinfunction "1_1") (pintype "passive"))
      (node (ref "U3") (pin "2") (pinfunction "SCL_2") (pintype "passive"))
    )
    (net (code "11") (name "/I2C3_SDA") (class "Default")
      (node (ref "R69") (pin "1") (pinfunction "1_1") (pintype "passive"))
      (node (ref "U3") (pin "3") (pinfunction "SDA_3") (pintype "passive"))
    )
    (net (code "12") (name "/IN_12V") (class "Default")
      (node (ref "F1") (pin "1") (pinfunction "1_1") (pintype "passive"))
      (node (ref "J7") (pin "2") (pinfunction "2_2") (pintype "passive"))
      (node (ref "J7") (pin "4") (pinfunction "4_4") (pintype "passive"))
      (node (ref "J8") (pin "1") (pinfunction "1_1") (pintype "passive"))
    )
    (net (code "13") (name "/PGOOD1") (class "Default")
      (node (ref "R67") (pin "1") (pinfunction "1_1") (pintype "passive"))
      (node (ref "U3") (pin "26") (pinfunction "PGOOD1_26") (pintype "passive"))
    )
    (net (code "14") (name "/PGOOD2") (class "Default")
      (node (ref "R66") (pin "1") (pinfunction "1_1") (pintype "passive"))
      (node (ref "U3") (pin "27") (pinfunction "PGOOD2_27") (pintype "passive"))
    )
    (net (code "15") (name "/SW2COMP") (class "Default")
      (node (ref "C182") (pin "2") (pinfunction "2_2") (pintype "passive"))
      (node (ref "R78") (pin "2") (pinfunction "2_2") (pintype "passive"))
      (node (ref "U3") (pin "5") (pinfunction "SW2COMP_5") (pintype "passive"))
    )
    (net (code "16") (name "/SW2GHS") (class "Default")
      (node (ref "Q2") (pin "2") (pinfunction "G1_2") (pintype "passive"))
      (node (ref "R65") (pin "1") (pinfunction "1_1") (pintype "passive"))
      (node (ref "U3") (pin "11") (pinfunction "SW2GHS_11") (pintype "passive"))
    )
    (net (code "17") (name "/SW2LX") (class "Default")
      (node (ref "C160") (pin "1") (pinfunction "1_1") (pintype "passive"))
      (node (ref "L11") (pin "1") (pinfunction "1_1") (pintype "passive"))
      (node (ref "Q2") (pin "1") (pinfunction "S1_1") (pintype "passive"))
      (node (ref "Q2") (pin "10") (pinfunction "D2_3_10") (pintype "passive"))
      (node (ref "Q2") (pin "5") (pinfunction "D2_1_5") (pintype "passive"))
      (node (ref "Q2") (pin "6") (pinfunction "D2_2_6") (pintype "passive"))
      (node (ref "R65") (pin "2") (pinfunction "2_2") (pintype "passive"))
      (node (ref "U3") (pin "10") (pinfunction "SW2LX_10") (pintype "passive"))
    )
    (net (code "18") (name "/SWCSN") (class "Default")
      (node (ref "R64") (pin "I2") (pinfunction "I2_I2") (pintype "passive"))
      (node (ref "U3") (pin "7") (pinfunction "SW2CSN_7") (pintype "passive"))
    )
    (net (code "19") (name "/SWCSP") (class "Default")
      (node (ref "Q2") (pin "4") (pinfunction "G2_4") (pintype "passive"))
      (node (ref "R64") (pin "E1") (pinfunction "E1_E1") (pintype "passive"))
      (node (ref "U3") (pin "8") (pinfunction "SW2CSP_8") (pintype "passive"))
      (node (ref "U3") (pin "9") (pinfunction "SW2GLS_9") (pintype "passive"))
    )
    (net (code "20") (name "/VDDOTP") (class "Default")
      (node (ref "R70") (pin "1") (pinfunction "1_1") (pintype "passive"))
      (node (ref "R72") (pin "2") (pinfunction "2_2") (pintype "passive"))
      (node (ref "TP38") (pin "1") (pinfunction "1_1") (pintype "passive"))
      (node (ref "U3") (pin "4") (pinfunction "GPIO1/VDDOTP_4") (pintype "passive"))
    )
    (net (code "21") (name "/VDIG") (class "Default")
      (node (ref "C172") (pin "2") (pinfunction "2_2") (pintype "passive"))
      (node (ref "U3") (pin "28") (pinfunction "VDIG_28") (pintype "passive"))
    )
    (net (code "23") (name "3V3_PS") (class "Default")
      (node (ref "C153") (pin "2") (pinfunction "2_2") (pintype "passive"))
      (node (ref "C154") (pin "2") (pinfunction "2_2") (pintype "passive"))
      (node (ref "C155") (pin "2") (pinfunction "2_2") (pintype "passive"))
      (node (ref "C156") (pin "2") (pinfunction "2_2") (pintype "passive"))
      (node (ref "C157") (pin "2") (pinfunction "2_2") (pintype "passive"))
      (node (ref "C158") (pin "2") (pinfunction "2_2") (pintype "passive"))
      (node (ref "R64") (pin "E2") (pinfunction "E2_E2") (pintype "passive"))
      (node (ref "R66") (pin "2") (pinfunction "2_2") (pintype "passive"))
      (node (ref "R67") (pin "2") (pinfunction "2_2") (pintype "passive"))
      (node (ref "R68") (pin "2") (pinfunction "2_2") (pintype "passive"))
      (node (ref "R69") (pin "2") (pinfunction "2_2") (pintype "passive"))
      (node (ref "R70") (pin "2") (pinfunction "2_2") (pintype "passive"))
      (node (ref "R71") (pin "2") (pinfunction "2_2") (pintype "passive"))
      (node (ref "R73") (pin "2") (pinfunction "2_2") (pintype "passive"))
      (node (ref "TP36") (pin "1") (pinfunction "1_1") (pintype "passive"))
      (node (ref "U3") (pin "1") (pinfunction "VDDIO_1") (pintype "passive"))
      (node (ref "U3") (pin "6") (pinfunction "SW2FB_6") (pintype "passive"))
    )
    (net (code "24") (name "5V0_PS") (class "Default")
      (node (ref "C161") (pin "2") (pinfunction "2_2") (pintype "passive"))
      (node (ref "C162") (pin "2") (pinfunction "2_2") (pintype "passive"))
      (node (ref "C163") (pin "2") (pinfunction "2_2") (pintype "passive"))
      (node (ref "C164") (pin "2") (pinfunction "2_2") (pintype "passive"))
      (node (ref "C165") (pin "2") (pinfunction "2_2") (pintype "passive"))
      (node (ref "C166") (pin "2") (pinfunction "2_2") (pintype "passive"))
      (node (ref "C167") (pin "2") (pinfunction "2_2") (pintype "passive"))
      (node (ref "C168") (pin "2") (pinfunction "2_2") (pintype "passive"))
      (node (ref "C173") (pin "2") (pinfunction "2_2") (pintype "passive"))
      (node (ref "C174") (pin "2") (pinfunction "2_2") (pintype "passive"))
      (node (ref "C175") (pin "2") (pinfunction "2_2") (pintype "passive"))
      (node (ref "C176") (pin "2") (pinfunction "2_2") (pintype "passive"))
      (node (ref "C177") (pin "2") (pinfunction "2_2") (pintype "passive"))
      (node (ref "C178") (pin "2") (pinfunction "2_2") (pintype "passive"))
      (node (ref "C179") (pin "2") (pinfunction "2_2") (pintype "passive"))
      (node (ref "C180") (pin "2") (pinfunction "2_2") (pintype "passive"))
      (node (ref "C181") (pin "2") (pinfunction "2_2") (pintype "passive"))
      (node (ref "L12") (pin "2") (pinfunction "2_2") (pintype "passive"))
      (node (ref "R74") (pin "2") (pinfunction "2_2") (pintype "passive"))
      (node (ref "R75") (pin "1") (pinfunction "1_1") (pintype "passive"))
      (node (ref "TP37") (pin "1") (pinfunction "1_1") (pintype "passive"))
      (node (ref "U3") (pin "25") (pinfunction "SW1FB_25") (pintype "passive"))
    )
    (net (code "25") (name "12V0") (class "Default")
      (node (ref "C149") (pin "2") (pinfunction "2_2") (pintype "passive"))
      (node (ref "C152") (pin "2") (pinfunction "2_2") (pintype "passive"))
      (node (ref "C159") (pin "2") (pinfunction "2_2") (pintype "passive"))
      (node (ref "Q2") (pin "7") (pinfunction "D1_1_7") (pintype "passive"))
      (node (ref "Q2") (pin "8") (pinfunction "D1_2_8") (pintype "passive"))
      (node (ref "Q2") (pin "9") (pinfunction "D1_3_9") (pintype "passive"))
      (node (ref "R63") (pin "2") (pinfunction "2_2") (pintype "passive"))
      (node (ref "TP35") (pin "1") (pinfunction "1_1") (pintype "passive"))
      (node (ref "U3") (pin "18") (pinfunction "SW1IN_1_18") (pintype "passive"))
      (node (ref "U3") (pin "19") (pinfunction "SW1IN_2_19") (pintype "passive"))
      (node (ref "U3") (pin "32") (pinfunction "VIN_32") (pintype "passive"))
    )
    (net (code "26") (name "FLT_12V") (class "Default")
      (node (ref "C151") (pin "1") (pinfunction "1_1") (pintype "passive"))
      (node (ref "FL1") (pin "2") (pinfunction "CB_2") (pintype "passive"))
      (node (ref "R63") (pin "1") (pinfunction "1_1") (pintype "passive"))
      (node (ref "TP34") (pin "1") (pinfunction "1_1") (pintype "passive"))
    )
    (net (code "27") (name "GND") (class "Default")
      (node (ref "C149") (pin "1") (pinfunction "1_1") (pintype "passive"))
      (node (ref "C150") (pin "2") (pinfunction "2_2") (pintype "passive"))
      (node (ref "C151") (pin "2") (pinfunction "2_2") (pintype "passive"))
      (node (ref "C152") (pin "1") (pinfunction "1_1") (pintype "passive"))
      (node (ref "C153") (pin "1") (pinfunction "1_1") (pintype "passive"))
      (node (ref "C154") (pin "1") (pinfunction "1_1") (pintype "passive"))
      (node (ref "C155") (pin "1") (pinfunction "1_1") (pintype "passive"))
      (node (ref "C156") (pin "1") (pinfunction "1_1") (pintype "passive"))
      (node (ref "C157") (pin "1") (pinfunction "1_1") (pintype "passive"))
      (node (ref "C158") (pin "1") (pinfunction "1_1") (pintype "passive"))
      (node (ref "C159") (pin "1") (pinfunction "1_1") (pintype "passive"))
      (node (ref "C161") (pin "1") (pinfunction "1_1") (pintype "passive"))
      (node (ref "C162") (pin "1") (pinfunction "1_1") (pintype "passive"))
      (node (ref "C163") (pin "1") (pinfunction "1_1") (pintype "passive"))
      (node (ref "C164") (pin "1") (pinfunction "1_1") (pintype "passive"))
      (node (ref "C165") (pin "1") (pinfunction "1_1") (pintype "passive"))
      (node (ref "C166") (pin "1") (pinfunction "1_1") (pintype "passive"))
      (node (ref "C167") (pin "1") (pinfunction "1_1") (pintype "passive"))
      (node (ref "C168") (pin "1") (pinfunction "1_1") (pintype "passive"))
      (node (ref "C170") (pin "1") (pinfunction "1_1") (pintype "passive"))
      (node (ref "C171") (pin "1") (pinfunction "1_1") (pintype "passive"))
      (node (ref "C172") (pin "1") (pinfunction "1_1") (pintype "passive"))
      (node (ref "C173") (pin "1") (pinfunction "1_1") (pintype "passive"))
      (node (ref "C174") (pin "1") (pinfunction "1_1") (pintype "passive"))
      (node (ref "C175") (pin "1") (pinfunction "1_1") (pintype "passive"))
      (node (ref "C176") (pin "1") (pinfunction "1_1") (pintype "passive"))
      (node (ref "C177") (pin "1") (pinfunction "1_1") (pintype "passive"))
      (node (ref "C178") (pin "1") (pinfunction "1_1") (pintype "passive"))
      (node (ref "C179") (pin "1") (pinfunction "1_1") (pintype "passive"))
      (node (ref "C180") (pin "1") (pinfunction "1_1") (pintype "passive"))
      (node (ref "C181") (pin "1") (pinfunction "1_1") (pintype "passive"))
      (node (ref "C182") (pin "1") (pinfunction "1_1") (pintype "passive"))
      (node (ref "C183") (pin "1") (pinfunction "1_1") (pintype "passive"))
      (node (ref "D2") (pin "2") (pinfunction "A_2") (pintype "passive"))
      (node (ref "FL1") (pin "3") (pinfunction "PSG_3") (pintype "passive"))
      (node (ref "FL1") (pin "4") (pinfunction "CG_4") (pintype "passive"))
      (node (ref "FL1") (pin "5") (pinfunction "CG_5") (pintype "passive"))
      (node (ref "FL1") (pin "6") (pinfunction "CG_6") (pintype "passive"))
      (node (ref "J7") (pin "1") (pinfunction "1_1") (pintype "passive"))
      (node (ref "J7") (pin "3") (pinfunction "3_3") (pintype "passive"))
      (node (ref "J7") (pin "S1") (pinfunction "SHIELD_S1") (pintype "passive"))
      (node (ref "J7") (pin "S2") (pinfunction "SHIELD_S2") (pintype "passive"))
      (node (ref "J7") (pin "S3") (pinfunction "SHIELD_S3") (pintype "passive"))
      (node (ref "J8") (pin "2") (pinfunction "2_2") (pintype "passive"))
      (node (ref "Q2") (pin "3") (pinfunction "S2_3") (pintype "passive"))
      (node (ref "R72") (pin "1") (pinfunction "1_1") (pintype "passive"))
      (node (ref "R76") (pin "1") (pinfunction "1_1") (pintype "passive"))
      (node (ref "R77") (pin "1") (pinfunction "1_1") (pintype "passive"))
      (node (ref "R79") (pin "2") (pinfunction "2_2") (pintype "passive"))
      (node (ref "U3") (pin "13") (pinfunction "GPO3_13") (pintype "passive"))
      (node (ref "U3") (pin "14") (pinfunction "GPO2_14") (pintype "passive"))
      (node (ref "U3") (pin "31") (pinfunction "MODE/SYNCIN_31") (pintype "passive"))
      (node (ref "U3") (pin "33") (pinfunction "GND_33") (pintype "passive"))
      (node (ref "U3") (pin "34") (pinfunction "EP_1_34") (pintype "passive"))
      (node (ref "U3") (pin "35") (pinfunction "EP_2_35") (pintype "passive"))
      (node (ref "U3") (pin "36") (pinfunction "EP_3_36") (pintype "passive"))
      (node (ref "U3") (pin "37") (pinfunction "EP_4_37") (pintype "passive"))
    )
    (net (code "28") (name "Net-(C183-Pad2)") (class "Default")
      (node (ref "C183") (pin "2") (pinfunction "2_2") (pintype "passive"))
      (node (ref "R78") (pin "1") (pinfunction "1_1") (pintype "passive"))
    )
    (net (code "29") (name "Net-(L11-Pad2)") (class "Default")
      (node (ref "L11") (pin "2") (pinfunction "2_2") (pintype "passive"))
      (node (ref "R64") (pin "I1") (pinfunction "I1_I1") (pintype "passive"))
    )
    (net (code "30") (name "Net-(U3-SW1BOOT)") (class "Default")
      (node (ref "C169") (pin "1") (pinfunction "1_1") (pintype "passive"))
      (node (ref "U3") (pin "17") (pinfunction "SW1BOOT_17") (pintype "passive"))
    )
    (net (code "31") (name "Net-(U3-SW1LX_1)") (class "Default")
      (node (ref "C169") (pin "2") (pinfunction "2_2") (pintype "passive"))
      (node (ref "L12") (pin "1") (pinfunction "1_1") (pintype "passive"))
      (node (ref "U3") (pin "20") (pinfunction "SW1LX_1_20") (pintype "passive"))
      (node (ref "U3") (pin "21") (pinfunction "SW1LX_2_21") (pintype "passive"))
    )
    (net (code "32") (name "Net-(U3-SW2BO_OT)") (class "Default")
      (node (ref "C160") (pin "2") (pinfunction "2_2") (pintype "passive"))
      (node (ref "U3") (pin "12") (pinfunction "SW2BO_OT_12") (pintype "passive"))
    )
  )
)
